# vumeter-LM3915.net
KiCad netlist of a schematic drawn in EAGLE
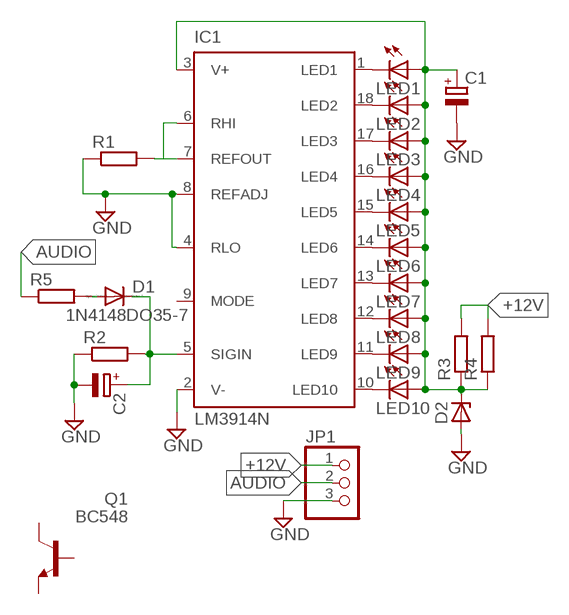
[diagram p0: schematic, sheet 1]

(export (version "E")
  (design (tool "Eeschema 10.0.6"))
  (components
    (comp (ref "C1")
      (value "CPOL-EUE2-4")
      (footprint "eagle-import:E2-4")
      (libsource (lib "eagle-import") (part "CPOL-EUE2-4"))
    )
    (comp (ref "C2")
      (value "CPOL-EUE2-4")
      (footprint "eagle-import:E2-4")
      (libsource (lib "eagle-import") (part "CPOL-EUE2-4"))
    )
    (comp (ref "D1")
      (value "1N4148DO35-7")
      (footprint "eagle-import:DO35-7")
      (libsource (lib "eagle-import") (part "1N4148DO35-7"))
    )
    (comp (ref "D2")
      (value "ZENER-DIODEZD-10")
      (footprint "eagle-import:ZDIO-10")
      (libsource (lib "eagle-import") (part "ZENER-DIODEZD-10"))
    )
    (comp (ref "IC1")
      (value "LM3914N")
      (footprint "eagle-import:DIL18")
      (libsource (lib "eagle-import") (part "LM391N4"))
    )
    (comp (ref "JP1")
      (value "PINHD-1X3")
      (footprint "eagle-import:1X03")
      (libsource (lib "eagle-import") (part "PINHD-1X3"))
    )
    (comp (ref "LED1")
      (value "LED3MM")
      (footprint "eagle-import:LED3MM")
      (libsource (lib "eagle-import") (part "LED3MM"))
    )
    (comp (ref "LED2")
      (value "LED3MM")
      (footprint "eagle-import:LED3MM")
      (libsource (lib "eagle-import") (part "LED3MM"))
    )
    (comp (ref "LED3")
      (value "LED3MM")
      (footprint "eagle-import:LED3MM")
      (libsource (lib "eagle-import") (part "LED3MM"))
    )
    (comp (ref "LED4")
      (value "LED3MM")
      (footprint "eagle-import:LED3MM")
      (libsource (lib "eagle-import") (part "LED3MM"))
    )
    (comp (ref "LED5")
      (value "LED3MM")
      (footprint "eagle-import:LED3MM")
      (libsource (lib "eagle-import") (part "LED3MM"))
    )
    (comp (ref "LED6")
      (value "LED3MM")
      (footprint "eagle-import:LED3MM")
      (libsource (lib "eagle-import") (part "LED3MM"))
    )
    (comp (ref "LED7")
      (value "LED3MM")
      (footprint "eagle-import:LED3MM")
      (libsource (lib "eagle-import") (part "LED3MM"))
    )
    (comp (ref "LED8")
      (value "LED3MM")
      (footprint "eagle-import:LED3MM")
      (libsource (lib "eagle-import") (part "LED3MM"))
    )
    (comp (ref "LED9")
      (value "LED3MM")
      (footprint "eagle-import:LED3MM")
      (libsource (lib "eagle-import") (part "LED3MM"))
    )
    (comp (ref "LED10")
      (value "LED3MM")
      (footprint "eagle-import:LED3MM")
      (libsource (lib "eagle-import") (part "LED3MM"))
    )
    (comp (ref "Q1")
      (value "BC548")
      (footprint "eagle-import:TO92-EBC")
      (libsource (lib "eagle-import") (part "BC548"))
    )
    (comp (ref "R1")
      (value "R-EU_0207/7")
      (footprint "eagle-import:0207_7")
      (libsource (lib "eagle-import") (part "R-EU_0207/7"))
    )
    (comp (ref "R2")
      (value "R-EU_0207/7")
      (footprint "eagle-import:0207_7")
      (libsource (lib "eagle-import") (part "R-EU_0207/7"))
    )
    (comp (ref "R3")
      (value "R-EU_0207/7")
      (footprint "eagle-import:0207_7")
      (libsource (lib "eagle-import") (part "R-EU_0207/7"))
    )
    (comp (ref "R4")
      (value "R-EU_0207/7")
      (footprint "eagle-import:0207_7")
      (libsource (lib "eagle-import") (part "R-EU_0207/7"))
    )
    (comp (ref "R5")
      (value "R-EU_0207/7")
      (footprint "eagle-import:0207_7")
      (libsource (lib "eagle-import") (part "R-EU_0207/7"))
    )
  )
  (nets
    (net (code "1") (name "+12V") (class "Default")
      (node (ref "JP1") (pin "1") (pinfunction "1_1") (pintype "passive"))
      (node (ref "R3") (pin "2") (pinfunction "2_2") (pintype "passive"))
      (node (ref "R4") (pin "2") (pinfunction "2_2") (pintype "passive"))
    )
    (net (code "2") (name "AUDIO") (class "Default")
      (node (ref "JP1") (pin "2") (pinfunction "2_2") (pintype "passive"))
      (node (ref "R5") (pin "1") (pinfunction "1_1") (pintype "passive"))
    )
    (net (code "3") (name "GND") (class "Default")
      (node (ref "C1") (pin "-") (pinfunction "-_-") (pintype "passive"))
      (node (ref "C2") (pin "-") (pinfunction "-_-") (pintype "passive"))
      (node (ref "D2") (pin "A") (pinfunction "A_A") (pintype "passive"))
      (node (ref "IC1") (pin "2") (pinfunction "V-_2") (pintype "power_in"))
      (node (ref "IC1") (pin "4") (pinfunction "RLO_4") (pintype "input"))
      (node (ref "IC1") (pin "8") (pinfunction "REFADJ_8") (pintype "passive"))
      (node (ref "JP1") (pin "3") (pinfunction "3_3") (pintype "passive"))
      (node (ref "R1") (pin "1") (pinfunction "1_1") (pintype "passive"))
      (node (ref "R2") (pin "1") (pinfunction "1_1") (pintype "passive"))
    )
    (net (code "4") (name "Net-(D1-PadA)") (class "Default")
      (node (ref "D1") (pin "A") (pinfunction "A_A") (pintype "passive"))
      (node (ref "R5") (pin "2") (pinfunction "2_2") (pintype "passive"))
    )
    (net (code "5") (name "Net-(IC1-LED1)") (class "Default")
      (node (ref "IC1") (pin "1") (pinfunction "LED1_1") (pintype "output"))
      (node (ref "LED1") (pin "K") (pinfunction "C_K") (pintype "passive"))
    )
    (net (code "6") (name "Net-(IC1-LED2)") (class "Default")
      (node (ref "IC1") (pin "18") (pinfunction "LED2_18") (pintype "output"))
      (node (ref "LED2") (pin "K") (pinfunction "C_K") (pintype "passive"))
    )
    (net (code "7") (name "Net-(IC1-LED3)") (class "Default")
      (node (ref "IC1") (pin "17") (pinfunction "LED3_17") (pintype "output"))
      (node (ref "LED3") (pin "K") (pinfunction "C_K") (pintype "passive"))
    )
    (net (code "8") (name "Net-(IC1-LED4)") (class "Default")
      (node (ref "IC1") (pin "16") (pinfunction "LED4_16") (pintype "output"))
      (node (ref "LED4") (pin "K") (pinfunction "C_K") (pintype "passive"))
    )
    (net (code "9") (name "Net-(IC1-LED5)") (class "Default")
      (node (ref "IC1") (pin "15") (pinfunction "LED5_15") (pintype "output"))
      (node (ref "LED5") (pin "K") (pinfunction "C_K") (pintype "passive"))
    )
    (net (code "10") (name "Net-(IC1-LED6)") (class "Default")
      (node (ref "IC1") (pin "14") (pinfunction "LED6_14") (pintype "output"))
      (node (ref "LED6") (pin "K") (pinfunction "C_K") (pintype "passive"))
    )
    (net (code "11") (name "Net-(IC1-LED7)") (class "Default")
      (node (ref "IC1") (pin "13") (pinfunction "LED7_13") (pintype "output"))
      (node (ref "LED7") (pin "K") (pinfunction "C_K") (pintype "passive"))
    )
    (net (code "12") (name "Net-(IC1-LED8)") (class "Default")
      (node (ref "IC1") (pin "12") (pinfunction "LED8_12") (pintype "output"))
      (node (ref "LED8") (pin "K") (pinfunction "C_K") (pintype "passive"))
    )
    (net (code "13") (name "Net-(IC1-LED9)") (class "Default")
      (node (ref "IC1") (pin "11") (pinfunction "LED9_11") (pintype "output"))
      (node (ref "LED9") (pin "K") (pinfunction "C_K") (pintype "passive"))
    )
    (net (code "14") (name "Net-(IC1-LED10)") (class "Default")
      (node (ref "IC1") (pin "10") (pinfunction "LED10_10") (pintype "output"))
      (node (ref "LED10") (pin "K") (pinfunction "C_K") (pintype "passive"))
    )
    (net (code "15") (name "Net-(IC1-REFOUT)") (class "Default")
      (node (ref "IC1") (pin "6") (pinfunction "RHI_6") (pintype "input"))
      (node (ref "IC1") (pin "7") (pinfunction "REFOUT_7") (pintype "output"))
      (node (ref "R1") (pin "2") (pinfunction "2_2") (pintype "passive"))
    )
    (net (code "16") (name "Net-(IC1-SIGIN)") (class "Default")
      (node (ref "C2") (pin "+") (pinfunction "+_+") (pintype "passive"))
      (node (ref "D1") (pin "C") (pinfunction "C_C") (pintype "passive"))
      (node (ref "IC1") (pin "5") (pinfunction "SIGIN_5") (pintype "input"))
      (node (ref "R2") (pin "2") (pinfunction "2_2") (pintype "passive"))
    )
    (net (code "17") (name "Net-(IC1-V+)") (class "Default")
      (node (ref "C1") (pin "+") (pinfunction "+_+") (pintype "passive"))
      (node (ref "D2") (pin "C") (pinfunction "C_C") (pintype "passive"))
      (node (ref "IC1") (pin "3") (pinfunction "V+_3") (pintype "power_in"))
      (node (ref "LED1") (pin "A") (pinfunction "A_A") (pintype "passive"))
      (node (ref "LED10") (pin "A") (pinfunction "A_A") (pintype "passive"))
      (node (ref "LED2") (pin "A") (pinfunction "A_A") (pintype "passive"))
      (node (ref "LED3") (pin "A") (pinfunction "A_A") (pintype "passive"))
      (node (ref "LED4") (pin "A") (pinfunction "A_A") (pintype "passive"))
      (node (ref "LED5") (pin "A") (pinfunction "A_A") (pintype "passive"))
      (node (ref "LED6") (pin "A") (pinfunction "A_A") (pintype "passive"))
      (node (ref "LED7") (pin "A") (pinfunction "A_A") (pintype "passive"))
      (node (ref "LED8") (pin "A") (pinfunction "A_A") (pintype "passive"))
      (node (ref "LED9") (pin "A") (pinfunction "A_A") (pintype "passive"))
      (node (ref "R3") (pin "1") (pinfunction "1_1") (pintype "passive"))
      (node (ref "R4") (pin "1") (pinfunction "1_1") (pintype "passive"))
    )
    (net (code "18") (name "unconnected-(IC1-MODE-Pad9)") (class "Default")
      (node (ref "IC1") (pin "9") (pinfunction "MODE_9") (pintype "input"))
    )
    (net (code "19") (name "unconnected-(Q1-PadB)") (class "Default")
      (node (ref "Q1") (pin "B") (pinfunction "B_B") (pintype "passive"))
    )
    (net (code "20") (name "unconnected-(Q1-PadC)") (class "Default")
      (node (ref "Q1") (pin "C") (pinfunction "C_C") (pintype "passive"))
    )
    (net (code "21") (name "unconnected-(Q1-PadE)") (class "Default")
      (node (ref "Q1") (pin "E") (pinfunction "E_E") (pintype "passive"))
    )
  )
)
